# Connectors.net
KiCad netlist of a schematic drawn in Altium Designer
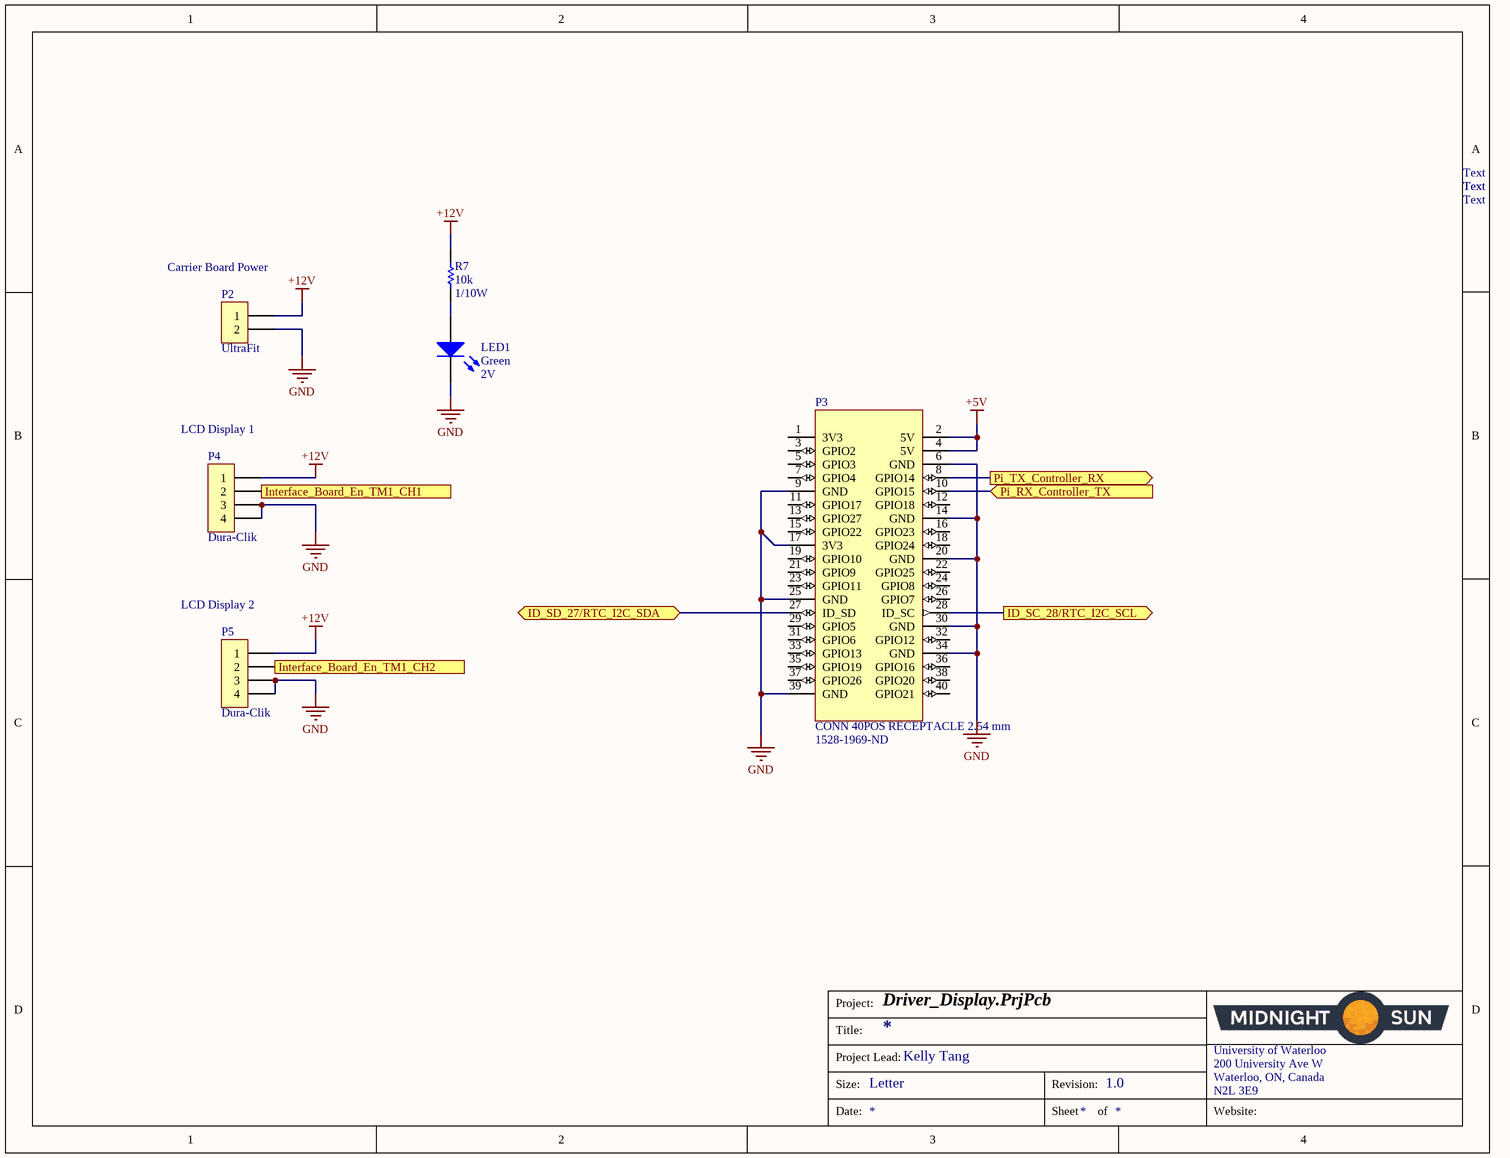
[diagram p0: Connectors.SchDoc]

(export (version "E")
  (design (tool "Eeschema 10.0.6"))
  (components
    (comp (ref "LED1")
      (value "LED GREEN CLEAR 2V 0603")
      (footprint "LED_0603")
      (description "Green 572nm LED Indication - Discrete 2V 0603 (1608 Metric)")
      (fields
        (field (name "MANUFACTURER") "Wurth Electronics Inc.")
        (field (name "MANUFACTURER PART NUMBER") "150060VS75000")
        (field (name "COLOR") "Green")
        (field (name "VOLTAGE - FORWARD (VF) (TYP)") "2V")
      )
      (libsource (lib "Schematic Diagrams") (part "LED GREEN CLEAR 2V 0603"))
    )
    (comp (ref "P2")
      (value "CONN 2POS ULTRA-FIT 0.138\"")
      (footprint "CONN, 2POS ULTRA-FIT")
      (description "2 Positions Header, Shrouded Connector 0.138\" (3.50mm) Through Hole Gold")
      (fields (field (name "VOLTAGE") "400V") (field (name "SERIES") "UltraFit"))
      (libsource (lib "Schematic Diagrams") (part "CONN 2POS ULTRA-FIT 0.138{dblquote}"))
    )
    (comp (ref "P3")
      (value "CONN 40POS RECEPTACLE 2.54 mm")
      (footprint "CONN 40POS RECEPTACLE 2.54 MM")
      (description "GPIO HEADER FOR RASPBERRYPI A+/B")
      (fields
        (field (name "MANUFACTURER") "Adafruit Industries")
        (field (name "MANUFACTURER PART NUMBER") "1992")
        (field (name "SUPPLIER PART NUMBER 1") "1528-1969-ND")
      )
      (libsource (lib "Schematic Diagrams") (part "CONN 40POS RECEPTACLE 2.54 mm"))
    )
    (comp (ref "P4")
      (value "Dura-Clik")
      (footprint "CONN, 4POS DURA-CLIK VERT")
      (description "4 Positions Header Connector 0.079\" (2.00mm) Surface Mount Tin")
      (fields
        (field (name "MANUFACTURER") "Molex, LLC")
        (field (name "MANUFACTURER PART NUMBER") "5600200420")
      )
      (libsource (lib "Schematic Diagrams") (part "CONN 4POS DURA-CLIK 0.079{dblquote}"))
    )
    (comp (ref "P5")
      (value "Dura-Clik")
      (footprint "CONN, 4POS DURA-CLIK VERT")
      (description "4 Positions Header Connector 0.079\" (2.00mm) Surface Mount Tin")
      (fields
        (field (name "MANUFACTURER") "Molex, LLC")
        (field (name "MANUFACTURER PART NUMBER") "5600200420")
      )
      (libsource (lib "Schematic Diagrams") (part "CONN 4POS DURA-CLIK 0.079{dblquote}"))
    )
    (comp (ref "R7")
      (value "RES 10K OHM 1% 1/10W 0603")
      (footprint "RES, 0603")
      (description "RES SMD 10K OHM 1% 1/10W 0603")
      (fields
        (field (name "TOLERANCE") "±1%")
        (field (name "RESISTANCE") "10k")
        (field (name "POWER") "1/10W")
      )
      (libsource (lib "Schematic Diagrams") (part "RES 10K OHM 1% 1/10W 0603"))
    )
  )
  (nets
    (net (code "1") (name "+5V") (class "Default")
      (node (ref "P3") (pin "2") (pinfunction "5V_2") (pintype "power_in"))
      (node (ref "P3") (pin "4") (pinfunction "5V_4") (pintype "power_in"))
    )
    (net (code "2") (name "+12V") (class "Default")
      (node (ref "P2") (pin "1") (pinfunction "1_1") (pintype "passive"))
      (node (ref "P4") (pin "1") (pinfunction "1_1") (pintype "passive"))
      (node (ref "P5") (pin "1") (pinfunction "1_1") (pintype "passive"))
      (node (ref "R7") (pin "2") (pinfunction "2_2") (pintype "passive"))
    )
    (net (code "3") (name "/ID_SC_28{slash}RTC_I2C_SCL") (class "Default")
      (node (ref "P3") (pin "28") (pinfunction "ID_SC_28") (pintype "output"))
    )
    (net (code "4") (name "/ID_SD_27{slash}RTC_I2C_SDA") (class "Default")
      (node (ref "P3") (pin "27") (pinfunction "ID_SD_27") (pintype "bidirectional"))
    )
    (net (code "5") (name "/Interface_Board_En_TM1_CH1") (class "Default")
      (node (ref "P4") (pin "2") (pinfunction "2_2") (pintype "passive"))
    )
    (net (code "6") (name "/Interface_Board_En_TM1_CH2") (class "Default")
      (node (ref "P5") (pin "2") (pinfunction "2_2") (pintype "passive"))
    )
    (net (code "7") (name "/Pi_RX_Controller_TX") (class "Default")
      (node (ref "P3") (pin "10") (pinfunction "GPIO15_10") (pintype "bidirectional"))
    )
    (net (code "8") (name "/Pi_TX_Controller_RX") (class "Default")
      (node (ref "P3") (pin "8") (pinfunction "GPIO14_8") (pintype "bidirectional"))
    )
    (net (code "9") (name "GND") (class "Default")
      (node (ref "LED1") (pin "2") (pinfunction "K_2") (pintype "passive"))
      (node (ref "P2") (pin "2") (pinfunction "2_2") (pintype "passive"))
      (node (ref "P3") (pin "14") (pinfunction "GND_14") (pintype "power_in"))
      (node (ref "P3") (pin "17") (pinfunction "3V3_17") (pintype "power_in"))
      (node (ref "P3") (pin "20") (pinfunction "GND_20") (pintype "power_in"))
      (node (ref "P3") (pin "25") (pinfunction "GND_25") (pintype "power_in"))
      (node (ref "P3") (pin "30") (pinfunction "GND_30") (pintype "power_in"))
      (node (ref "P3") (pin "34") (pinfunction "GND_34") (pintype "power_in"))
      (node (ref "P3") (pin "39") (pinfunction "GND_39") (pintype "power_in"))
      (node (ref "P3") (pin "6") (pinfunction "GND_6") (pintype "power_in"))
      (node (ref "P3") (pin "9") (pinfunction "GND_9") (pintype "power_in"))
      (node (ref "P4") (pin "3") (pinfunction "3_3") (pintype "passive"))
      (node (ref "P4") (pin "4") (pinfunction "4_4") (pintype "passive"))
      (node (ref "P5") (pin "3") (pinfunction "3_3") (pintype "passive"))
      (node (ref "P5") (pin "4") (pinfunction "4_4") (pintype "passive"))
    )
    (net (code "10") (name "Net-(LED1-A)") (class "Default")
      (node (ref "LED1") (pin "1") (pinfunction "A_1") (pintype "passive"))
      (node (ref "R7") (pin "1") (pinfunction "1_1") (pintype "passive"))
    )
    (net (code "11") (name "unconnected-(P3-3V3-Pad1)") (class "Default")
      (node (ref "P3") (pin "1") (pinfunction "3V3_1") (pintype "power_in"))
    )
    (net (code "12") (name "unconnected-(P3-GPIO2-Pad3)") (class "Default")
      (node (ref "P3") (pin "3") (pinfunction "GPIO2_3") (pintype "bidirectional"))
    )
    (net (code "13") (name "unconnected-(P3-GPIO3-Pad5)") (class "Default")
      (node (ref "P3") (pin "5") (pinfunction "GPIO3_5") (pintype "bidirectional"))
    )
    (net (code "14") (name "unconnected-(P3-GPIO4-Pad7)") (class "Default")
      (node (ref "P3") (pin "7") (pinfunction "GPIO4_7") (pintype "bidirectional"))
    )
    (net (code "15") (name "unconnected-(P3-GPIO5-Pad29)") (class "Default")
      (node (ref "P3") (pin "29") (pinfunction "GPIO5_29") (pintype "bidirectional"))
    )
    (net (code "16") (name "unconnected-(P3-GPIO6-Pad31)") (class "Default")
      (node (ref "P3") (pin "31") (pinfunction "GPIO6_31") (pintype "bidirectional"))
    )
    (net (code "17") (name "unconnected-(P3-GPIO7-Pad26)") (class "Default")
      (node (ref "P3") (pin "26") (pinfunction "GPIO7_26") (pintype "bidirectional"))
    )
    (net (code "18") (name "unconnected-(P3-GPIO8-Pad24)") (class "Default")
      (node (ref "P3") (pin "24") (pinfunction "GPIO8_24") (pintype "bidirectional"))
    )
    (net (code "19") (name "unconnected-(P3-GPIO9-Pad21)") (class "Default")
      (node (ref "P3") (pin "21") (pinfunction "GPIO9_21") (pintype "bidirectional"))
    )
    (net (code "20") (name "unconnected-(P3-GPIO10-Pad19)") (class "Default")
      (node (ref "P3") (pin "19") (pinfunction "GPIO10_19") (pintype "bidirectional"))
    )
    (net (code "21") (name "unconnected-(P3-GPIO11-Pad23)") (class "Default")
      (node (ref "P3") (pin "23") (pinfunction "GPIO11_23") (pintype "bidirectional"))
    )
    (net (code "22") (name "unconnected-(P3-GPIO12-Pad32)") (class "Default")
      (node (ref "P3") (pin "32") (pinfunction "GPIO12_32") (pintype "bidirectional"))
    )
    (net (code "23") (name "unconnected-(P3-GPIO13-Pad33)") (class "Default")
      (node (ref "P3") (pin "33") (pinfunction "GPIO13_33") (pintype "bidirectional"))
    )
    (net (code "24") (name "unconnected-(P3-GPIO16-Pad36)") (class "Default")
      (node (ref "P3") (pin "36") (pinfunction "GPIO16_36") (pintype "bidirectional"))
    )
    (net (code "25") (name "unconnected-(P3-GPIO17-Pad11)") (class "Default")
      (node (ref "P3") (pin "11") (pinfunction "GPIO17_11") (pintype "bidirectional"))
    )
    (net (code "26") (name "unconnected-(P3-GPIO18-Pad12)") (class "Default")
      (node (ref "P3") (pin "12") (pinfunction "GPIO18_12") (pintype "bidirectional"))
    )
    (net (code "27") (name "unconnected-(P3-GPIO19-Pad35)") (class "Default")
      (node (ref "P3") (pin "35") (pinfunction "GPIO19_35") (pintype "bidirectional"))
    )
    (net (code "28") (name "unconnected-(P3-GPIO20-Pad38)") (class "Default")
      (node (ref "P3") (pin "38") (pinfunction "GPIO20_38") (pintype "bidirectional"))
    )
    (net (code "29") (name "unconnected-(P3-GPIO21-Pad40)") (class "Default")
      (node (ref "P3") (pin "40") (pinfunction "GPIO21_40") (pintype "bidirectional"))
    )
    (net (code "30") (name "unconnected-(P3-GPIO22-Pad15)") (class "Default")
      (node (ref "P3") (pin "15") (pinfunction "GPIO22_15") (pintype "bidirectional"))
    )
    (net (code "31") (name "unconnected-(P3-GPIO23-Pad16)") (class "Default")
      (node (ref "P3") (pin "16") (pinfunction "GPIO23_16") (pintype "bidirectional"))
    )
    (net (code "32") (name "unconnected-(P3-GPIO24-Pad18)") (class "Default")
      (node (ref "P3") (pin "18") (pinfunction "GPIO24_18") (pintype "bidirectional"))
    )
    (net (code "33") (name "unconnected-(P3-GPIO25-Pad22)") (class "Default")
      (node (ref "P3") (pin "22") (pinfunction "GPIO25_22") (pintype "bidirectional"))
    )
    (net (code "34") (name "unconnected-(P3-GPIO26-Pad37)") (class "Default")
      (node (ref "P3") (pin "37") (pinfunction "GPIO26_37") (pintype "bidirectional"))
    )
    (net (code "35") (name "unconnected-(P3-GPIO27-Pad13)") (class "Default")
      (node (ref "P3") (pin "13") (pinfunction "GPIO27_13") (pintype "bidirectional"))
    )
  )
)
